# untitled.net
KiCad netlist of a schematic drawn in EAGLE
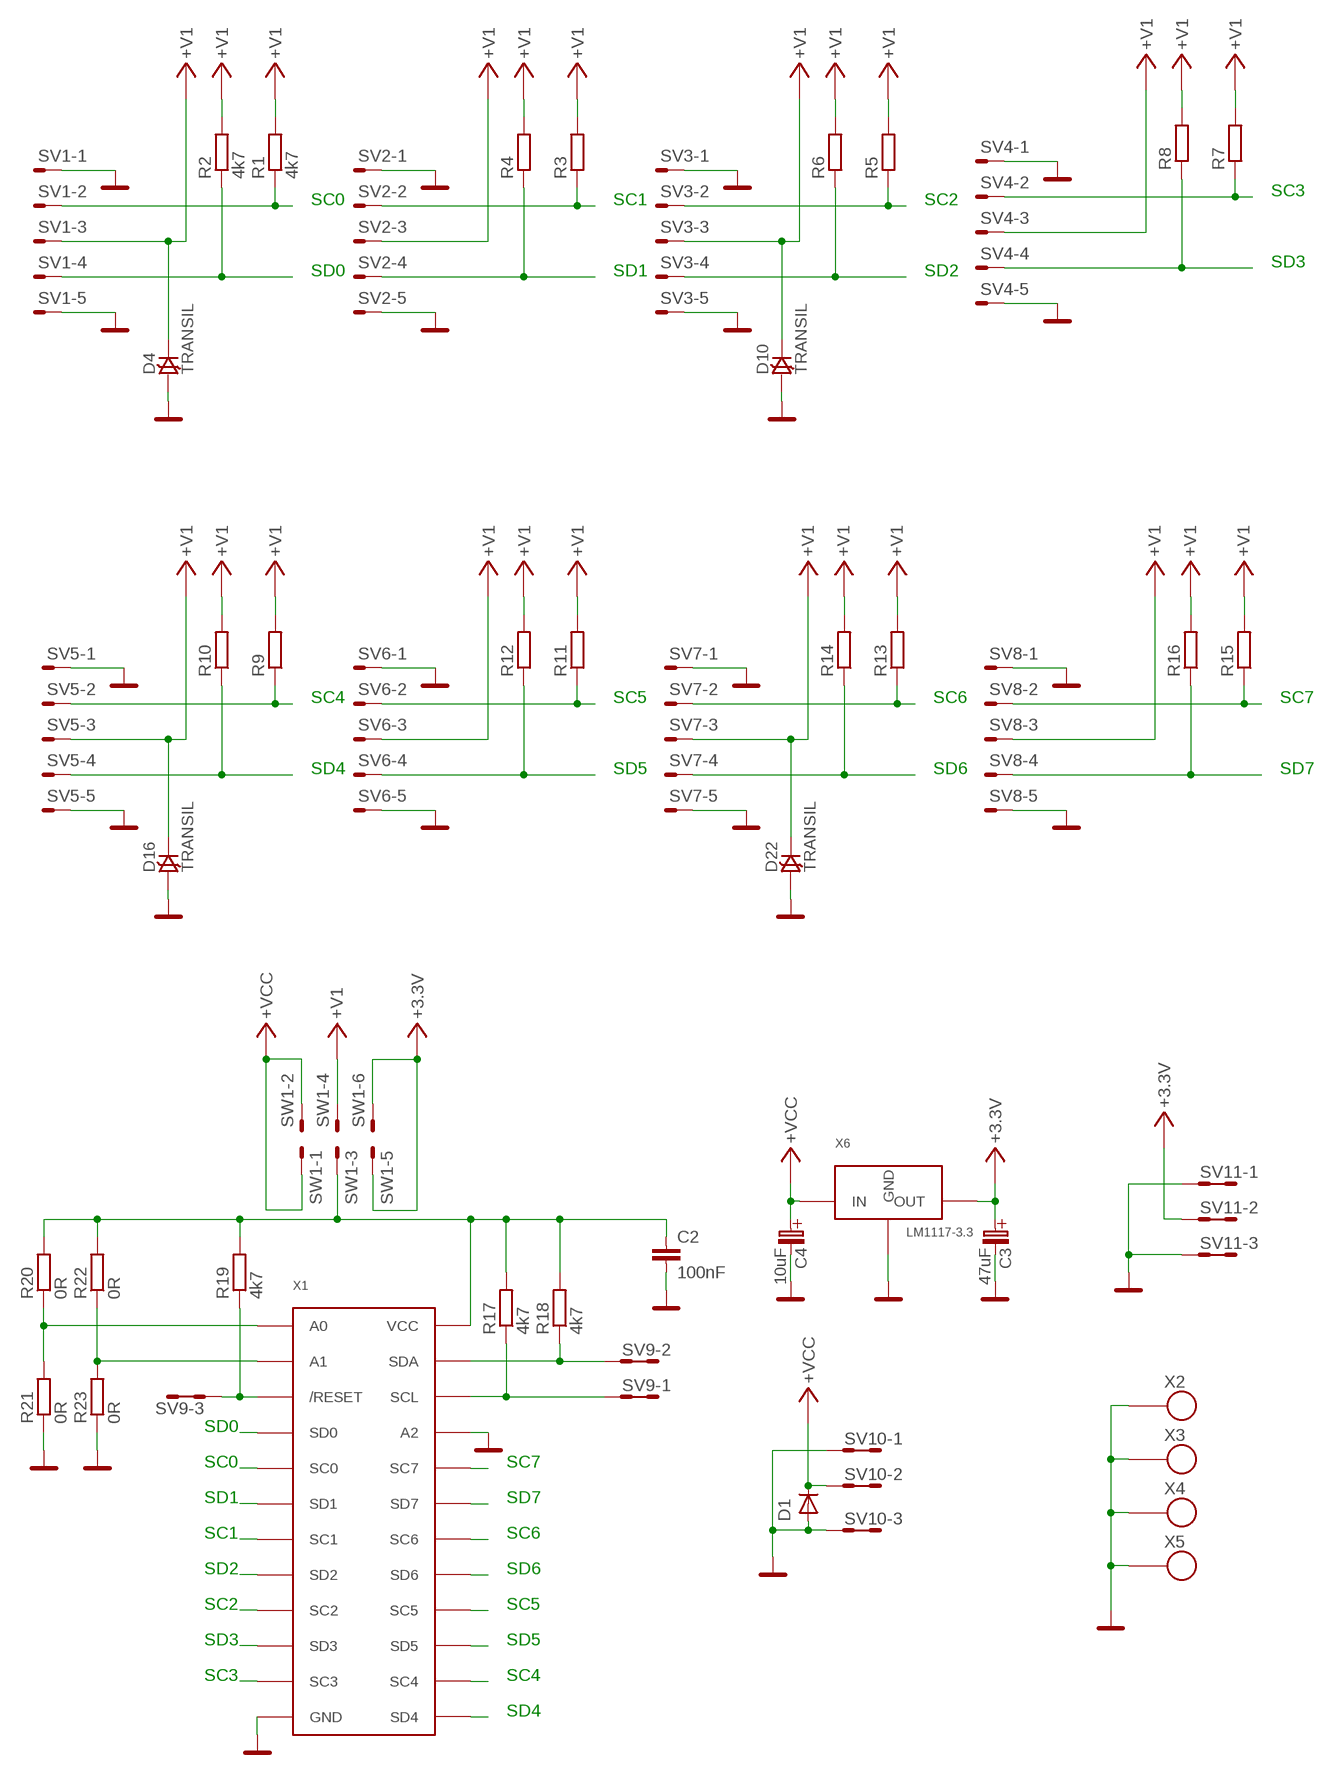
[diagram p0: schematic, sheet 1]

(export (version "E")
  (design (tool "Eeschema 10.0.6"))
  (components
    (comp (ref "C2")
      (value "100nF")
      (footprint "eagle-import:C0805")
      (libsource (lib "eagle-import") (part "C0805"))
    )
    (comp (ref "C3") (value "47uF") (footprint "eagle-import:C") (libsource (lib "eagle-import") (part "C")))
    (comp (ref "C4") (value "10uF") (footprint "eagle-import:B") (libsource (lib "eagle-import") (part "B")))
    (comp (ref "D1")
      (value "D-OB.SMA")
      (footprint "eagle-import:SMA")
      (libsource (lib "eagle-import") (part "D-OB.SMA"))
    )
    (comp (ref "D4")
      (value "TRANSIL")
      (footprint "eagle-import:SMA")
      (libsource (lib "eagle-import") (part "D-TRANSIL-SMA"))
    )
    (comp (ref "D10")
      (value "TRANSIL")
      (footprint "eagle-import:SMA")
      (libsource (lib "eagle-import") (part "D-TRANSIL-SMA"))
    )
    (comp (ref "D16")
      (value "TRANSIL")
      (footprint "eagle-import:SMA")
      (libsource (lib "eagle-import") (part "D-TRANSIL-SMA"))
    )
    (comp (ref "D22")
      (value "TRANSIL")
      (footprint "eagle-import:SMA")
      (libsource (lib "eagle-import") (part "D-TRANSIL-SMA"))
    )
    (comp (ref "R1")
      (value "4k7")
      (footprint "eagle-import:0805")
      (libsource (lib "eagle-import") (part "R0805"))
    )
    (comp (ref "R2")
      (value "4k7")
      (footprint "eagle-import:0805")
      (libsource (lib "eagle-import") (part "R0805"))
    )
    (comp (ref "R3")
      (value "R0805")
      (footprint "eagle-import:0805")
      (libsource (lib "eagle-import") (part "R0805"))
    )
    (comp (ref "R4")
      (value "R0805")
      (footprint "eagle-import:0805")
      (libsource (lib "eagle-import") (part "R0805"))
    )
    (comp (ref "R5")
      (value "R0805")
      (footprint "eagle-import:0805")
      (libsource (lib "eagle-import") (part "R0805"))
    )
    (comp (ref "R6")
      (value "R0805")
      (footprint "eagle-import:0805")
      (libsource (lib "eagle-import") (part "R0805"))
    )
    (comp (ref "R7")
      (value "R0805")
      (footprint "eagle-import:0805")
      (libsource (lib "eagle-import") (part "R0805"))
    )
    (comp (ref "R8")
      (value "R0805")
      (footprint "eagle-import:0805")
      (libsource (lib "eagle-import") (part "R0805"))
    )
    (comp (ref "R9")
      (value "R0805")
      (footprint "eagle-import:0805")
      (libsource (lib "eagle-import") (part "R0805"))
    )
    (comp (ref "R10")
      (value "R0805")
      (footprint "eagle-import:0805")
      (libsource (lib "eagle-import") (part "R0805"))
    )
    (comp (ref "R11")
      (value "R0805")
      (footprint "eagle-import:0805")
      (libsource (lib "eagle-import") (part "R0805"))
    )
    (comp (ref "R12")
      (value "R0805")
      (footprint "eagle-import:0805")
      (libsource (lib "eagle-import") (part "R0805"))
    )
    (comp (ref "R13")
      (value "R0805")
      (footprint "eagle-import:0805")
      (libsource (lib "eagle-import") (part "R0805"))
    )
    (comp (ref "R14")
      (value "R0805")
      (footprint "eagle-import:0805")
      (libsource (lib "eagle-import") (part "R0805"))
    )
    (comp (ref "R15")
      (value "R0805")
      (footprint "eagle-import:0805")
      (libsource (lib "eagle-import") (part "R0805"))
    )
    (comp (ref "R16")
      (value "R0805")
      (footprint "eagle-import:0805")
      (libsource (lib "eagle-import") (part "R0805"))
    )
    (comp (ref "R17")
      (value "4k7")
      (footprint "eagle-import:0805")
      (libsource (lib "eagle-import") (part "R0805"))
    )
    (comp (ref "R18")
      (value "4k7")
      (footprint "eagle-import:0805")
      (libsource (lib "eagle-import") (part "R0805"))
    )
    (comp (ref "R19")
      (value "4k7")
      (footprint "eagle-import:0805")
      (libsource (lib "eagle-import") (part "R0805"))
    )
    (comp (ref "R20")
      (value "0R")
      (footprint "eagle-import:0805")
      (libsource (lib "eagle-import") (part "R0805"))
    )
    (comp (ref "R21")
      (value "0R")
      (footprint "eagle-import:0805")
      (libsource (lib "eagle-import") (part "R0805"))
    )
    (comp (ref "R22")
      (value "0R")
      (footprint "eagle-import:0805")
      (libsource (lib "eagle-import") (part "R0805"))
    )
    (comp (ref "R23")
      (value "0R")
      (footprint "eagle-import:0805")
      (libsource (lib "eagle-import") (part "R0805"))
    )
    (comp (ref "SV1")
      (value "MA05-1")
      (footprint "eagle-import:MA05-1")
      (libsource (lib "eagle-import") (part "MA05-1"))
    )
    (comp (ref "SV2")
      (value "MA05-1")
      (footprint "eagle-import:MA05-1")
      (libsource (lib "eagle-import") (part "MA05-1"))
    )
    (comp (ref "SV3")
      (value "MA05-1")
      (footprint "eagle-import:MA05-1")
      (libsource (lib "eagle-import") (part "MA05-1"))
    )
    (comp (ref "SV4")
      (value "MA05-1")
      (footprint "eagle-import:MA05-1")
      (libsource (lib "eagle-import") (part "MA05-1"))
    )
    (comp (ref "SV5")
      (value "MA05-1")
      (footprint "eagle-import:MA05-1")
      (libsource (lib "eagle-import") (part "MA05-1"))
    )
    (comp (ref "SV6")
      (value "MA05-1")
      (footprint "eagle-import:MA05-1")
      (libsource (lib "eagle-import") (part "MA05-1"))
    )
    (comp (ref "SV7")
      (value "MA05-1")
      (footprint "eagle-import:MA05-1")
      (libsource (lib "eagle-import") (part "MA05-1"))
    )
    (comp (ref "SV8")
      (value "MA05-1")
      (footprint "eagle-import:MA05-1")
      (libsource (lib "eagle-import") (part "MA05-1"))
    )
    (comp (ref "SV9")
      (value "MA03-2")
      (footprint "eagle-import:MA03-2")
      (libsource (lib "eagle-import") (part "MA03-2"))
    )
    (comp (ref "SV10")
      (value "MA03-2")
      (footprint "eagle-import:MA03-2")
      (libsource (lib "eagle-import") (part "MA03-2"))
    )
    (comp (ref "SV11")
      (value "MA03-2")
      (footprint "eagle-import:MA03-2")
      (libsource (lib "eagle-import") (part "MA03-2"))
    )
    (comp (ref "SW1")
      (value "MA03-3")
      (footprint "eagle-import:MA03-2")
      (libsource (lib "eagle-import") (part "MA03-3"))
    )
    (comp (ref "X1")
      (value "TCA9548A")
      (footprint "eagle-import:TSS0P24")
      (libsource (lib "eagle-import") (part "TCA9548A"))
    )
    (comp (ref "X2")
      (value "SROUB3M")
      (footprint "eagle-import:SROUB3M")
      (libsource (lib "eagle-import") (part "SROUB3M"))
    )
    (comp (ref "X3")
      (value "SROUB3M")
      (footprint "eagle-import:SROUB3M")
      (libsource (lib "eagle-import") (part "SROUB3M"))
    )
    (comp (ref "X4")
      (value "SROUB3M")
      (footprint "eagle-import:SROUB3M")
      (libsource (lib "eagle-import") (part "SROUB3M"))
    )
    (comp (ref "X5")
      (value "SROUB3M")
      (footprint "eagle-import:SROUB3M")
      (libsource (lib "eagle-import") (part "SROUB3M"))
    )
    (comp (ref "X6")
      (value "LM1117-3.3")
      (footprint "eagle-import:SOT223")
      (libsource (lib "eagle-import") (part "LM1117"))
    )
  )
  (nets
    (net (code "1") (name "+3.3V") (class "Default")
      (node (ref "C3") (pin "+") (pinfunction "C_EL+_+") (pintype "passive"))
      (node (ref "SV11") (pin "3") (pinfunction "K_3") (pintype "passive"))
      (node (ref "SV11") (pin "4") (pinfunction "K_4") (pintype "passive"))
      (node (ref "SW1") (pin "5") (pinfunction "P$1_5") (pintype "passive"))
      (node (ref "SW1") (pin "6") (pinfunction "P$1_6") (pintype "passive"))
      (node (ref "X6") (pin "2") (pinfunction "OUT_2") (pintype "bidirectional"))
      (node (ref "X6") (pin "4") (pinfunction "OUT_4") (pintype "bidirectional"))
    )
    (net (code "2") (name "+V1") (class "Default")
      (node (ref "D10") (pin "K") (pinfunction "K_K") (pintype "passive"))
      (node (ref "D16") (pin "K") (pinfunction "K_K") (pintype "passive"))
      (node (ref "D22") (pin "K") (pinfunction "K_K") (pintype "passive"))
      (node (ref "D4") (pin "K") (pinfunction "K_K") (pintype "passive"))
      (node (ref "R1") (pin "2") (pinfunction "2_2") (pintype "passive"))
      (node (ref "R10") (pin "2") (pinfunction "2_2") (pintype "passive"))
      (node (ref "R11") (pin "2") (pinfunction "2_2") (pintype "passive"))
      (node (ref "R12") (pin "2") (pinfunction "2_2") (pintype "passive"))
      (node (ref "R13") (pin "2") (pinfunction "2_2") (pintype "passive"))
      (node (ref "R14") (pin "2") (pinfunction "2_2") (pintype "passive"))
      (node (ref "R15") (pin "2") (pinfunction "2_2") (pintype "passive"))
      (node (ref "R16") (pin "2") (pinfunction "2_2") (pintype "passive"))
      (node (ref "R2") (pin "2") (pinfunction "2_2") (pintype "passive"))
      (node (ref "R3") (pin "2") (pinfunction "2_2") (pintype "passive"))
      (node (ref "R4") (pin "2") (pinfunction "2_2") (pintype "passive"))
      (node (ref "R5") (pin "2") (pinfunction "2_2") (pintype "passive"))
      (node (ref "R6") (pin "2") (pinfunction "2_2") (pintype "passive"))
      (node (ref "R7") (pin "2") (pinfunction "2_2") (pintype "passive"))
      (node (ref "R8") (pin "2") (pinfunction "2_2") (pintype "passive"))
      (node (ref "R9") (pin "2") (pinfunction "2_2") (pintype "passive"))
      (node (ref "SV1") (pin "3") (pinfunction "P$1_3") (pintype "passive"))
      (node (ref "SV2") (pin "3") (pinfunction "P$1_3") (pintype "passive"))
      (node (ref "SV3") (pin "3") (pinfunction "P$1_3") (pintype "passive"))
      (node (ref "SV4") (pin "3") (pinfunction "P$1_3") (pintype "passive"))
      (node (ref "SV5") (pin "3") (pinfunction "P$1_3") (pintype "passive"))
      (node (ref "SV6") (pin "3") (pinfunction "P$1_3") (pintype "passive"))
      (node (ref "SV7") (pin "3") (pinfunction "P$1_3") (pintype "passive"))
      (node (ref "SV8") (pin "3") (pinfunction "P$1_3") (pintype "passive"))
      (node (ref "SW1") (pin "4") (pinfunction "P$1_4") (pintype "passive"))
    )
    (net (code "3") (name "+VCC") (class "Default")
      (node (ref "C4") (pin "+") (pinfunction "C_EL+_+") (pintype "passive"))
      (node (ref "D1") (pin "K") (pinfunction "C_K") (pintype "passive"))
      (node (ref "SV10") (pin "3") (pinfunction "K_3") (pintype "passive"))
      (node (ref "SV10") (pin "4") (pinfunction "K_4") (pintype "passive"))
      (node (ref "SW1") (pin "1") (pinfunction "P$1_1") (pintype "passive"))
      (node (ref "SW1") (pin "2") (pinfunction "P$1_2") (pintype "passive"))
      (node (ref "X6") (pin "3") (pinfunction "IN_3") (pintype "bidirectional"))
    )
    (net (code "4") (name "/SC0") (class "Default")
      (node (ref "R1") (pin "1") (pinfunction "1_1") (pintype "passive"))
      (node (ref "SV1") (pin "2") (pinfunction "P$1_2") (pintype "passive"))
      (node (ref "X1") (pin "5") (pinfunction "SC0_5") (pintype "bidirectional"))
    )
    (net (code "5") (name "/SC1") (class "Default")
      (node (ref "R3") (pin "1") (pinfunction "1_1") (pintype "passive"))
      (node (ref "SV2") (pin "2") (pinfunction "P$1_2") (pintype "passive"))
      (node (ref "X1") (pin "7") (pinfunction "SC1_7") (pintype "bidirectional"))
    )
    (net (code "6") (name "/SC2") (class "Default")
      (node (ref "R5") (pin "1") (pinfunction "1_1") (pintype "passive"))
      (node (ref "SV3") (pin "2") (pinfunction "P$1_2") (pintype "passive"))
      (node (ref "X1") (pin "9") (pinfunction "SC2_9") (pintype "bidirectional"))
    )
    (net (code "7") (name "/SC3") (class "Default")
      (node (ref "R7") (pin "1") (pinfunction "1_1") (pintype "passive"))
      (node (ref "SV4") (pin "2") (pinfunction "P$1_2") (pintype "passive"))
      (node (ref "X1") (pin "11") (pinfunction "SC3_11") (pintype "bidirectional"))
    )
    (net (code "8") (name "/SC4") (class "Default")
      (node (ref "R9") (pin "1") (pinfunction "1_1") (pintype "passive"))
      (node (ref "SV5") (pin "2") (pinfunction "P$1_2") (pintype "passive"))
      (node (ref "X1") (pin "14") (pinfunction "SC4_14") (pintype "bidirectional"))
    )
    (net (code "9") (name "/SC5") (class "Default")
      (node (ref "R11") (pin "1") (pinfunction "1_1") (pintype "passive"))
      (node (ref "SV6") (pin "2") (pinfunction "P$1_2") (pintype "passive"))
      (node (ref "X1") (pin "16") (pinfunction "SC5_16") (pintype "bidirectional"))
    )
    (net (code "10") (name "/SC6") (class "Default")
      (node (ref "R13") (pin "1") (pinfunction "1_1") (pintype "passive"))
      (node (ref "SV7") (pin "2") (pinfunction "P$1_2") (pintype "passive"))
      (node (ref "X1") (pin "18") (pinfunction "SC6_18") (pintype "bidirectional"))
    )
    (net (code "11") (name "/SC7") (class "Default")
      (node (ref "R15") (pin "1") (pinfunction "1_1") (pintype "passive"))
      (node (ref "SV8") (pin "2") (pinfunction "P$1_2") (pintype "passive"))
      (node (ref "X1") (pin "20") (pinfunction "SC7_20") (pintype "bidirectional"))
    )
    (net (code "12") (name "/SD0") (class "Default")
      (node (ref "R2") (pin "1") (pinfunction "1_1") (pintype "passive"))
      (node (ref "SV1") (pin "4") (pinfunction "P$1_4") (pintype "passive"))
      (node (ref "X1") (pin "4") (pinfunction "SD0_4") (pintype "bidirectional"))
    )
    (net (code "13") (name "/SD1") (class "Default")
      (node (ref "R4") (pin "1") (pinfunction "1_1") (pintype "passive"))
      (node (ref "SV2") (pin "4") (pinfunction "P$1_4") (pintype "passive"))
      (node (ref "X1") (pin "6") (pinfunction "SD1_6") (pintype "bidirectional"))
    )
    (net (code "14") (name "/SD2") (class "Default")
      (node (ref "R6") (pin "1") (pinfunction "1_1") (pintype "passive"))
      (node (ref "SV3") (pin "4") (pinfunction "P$1_4") (pintype "passive"))
      (node (ref "X1") (pin "8") (pinfunction "SD2_8") (pintype "bidirectional"))
    )
    (net (code "15") (name "/SD3") (class "Default")
      (node (ref "R8") (pin "1") (pinfunction "1_1") (pintype "passive"))
      (node (ref "SV4") (pin "4") (pinfunction "P$1_4") (pintype "passive"))
      (node (ref "X1") (pin "10") (pinfunction "SD3_10") (pintype "bidirectional"))
    )
    (net (code "16") (name "/SD4") (class "Default")
      (node (ref "R10") (pin "1") (pinfunction "1_1") (pintype "passive"))
      (node (ref "SV5") (pin "4") (pinfunction "P$1_4") (pintype "passive"))
      (node (ref "X1") (pin "13") (pinfunction "SD4_13") (pintype "bidirectional"))
    )
    (net (code "17") (name "/SD5") (class "Default")
      (node (ref "R12") (pin "1") (pinfunction "1_1") (pintype "passive"))
      (node (ref "SV6") (pin "4") (pinfunction "P$1_4") (pintype "passive"))
      (node (ref "X1") (pin "15") (pinfunction "SD5_15") (pintype "bidirectional"))
    )
    (net (code "18") (name "/SD6") (class "Default")
      (node (ref "R14") (pin "1") (pinfunction "1_1") (pintype "passive"))
      (node (ref "SV7") (pin "4") (pinfunction "P$1_4") (pintype "passive"))
      (node (ref "X1") (pin "17") (pinfunction "SD6_17") (pintype "bidirectional"))
    )
    (net (code "19") (name "/SD7") (class "Default")
      (node (ref "R16") (pin "1") (pinfunction "1_1") (pintype "passive"))
      (node (ref "SV8") (pin "4") (pinfunction "P$1_4") (pintype "passive"))
      (node (ref "X1") (pin "19") (pinfunction "SD7_19") (pintype "bidirectional"))
    )
    (net (code "20") (name "GND") (class "Default")
      (node (ref "C2") (pin "2") (pinfunction "2_2") (pintype "passive"))
      (node (ref "C3") (pin "-") (pinfunction "C_EL-_-") (pintype "passive"))
      (node (ref "C4") (pin "-") (pinfunction "C_EL-_-") (pintype "passive"))
      (node (ref "D1") (pin "A") (pinfunction "A_A") (pintype "passive"))
      (node (ref "D10") (pin "A") (pinfunction "A_A") (pintype "passive"))
      (node (ref "D16") (pin "A") (pinfunction "A_A") (pintype "passive"))
      (node (ref "D22") (pin "A") (pinfunction "A_A") (pintype "passive"))
      (node (ref "D4") (pin "A") (pinfunction "A_A") (pintype "passive"))
      (node (ref "R21") (pin "1") (pinfunction "1_1") (pintype "passive"))
      (node (ref "R23") (pin "1") (pinfunction "1_1") (pintype "passive"))
      (node (ref "SV1") (pin "1") (pinfunction "P$1_1") (pintype "passive"))
      (node (ref "SV1") (pin "5") (pinfunction "P$1_5") (pintype "passive"))
      (node (ref "SV10") (pin "1") (pinfunction "K_1") (pintype "passive"))
      (node (ref "SV10") (pin "2") (pinfunction "K_2") (pintype "passive"))
      (node (ref "SV10") (pin "5") (pinfunction "K_5") (pintype "passive"))
      (node (ref "SV10") (pin "6") (pinfunction "K_6") (pintype "passive"))
      (node (ref "SV11") (pin "1") (pinfunction "K_1") (pintype "passive"))
      (node (ref "SV11") (pin "2") (pinfunction "K_2") (pintype "passive"))
      (node (ref "SV11") (pin "5") (pinfunction "K_5") (pintype "passive"))
      (node (ref "SV11") (pin "6") (pinfunction "K_6") (pintype "passive"))
      (node (ref "SV2") (pin "1") (pinfunction "P$1_1") (pintype "passive"))
      (node (ref "SV2") (pin "5") (pinfunction "P$1_5") (pintype "passive"))
      (node (ref "SV3") (pin "1") (pinfunction "P$1_1") (pintype "passive"))
      (node (ref "SV3") (pin "5") (pinfunction "P$1_5") (pintype "passive"))
      (node (ref "SV4") (pin "1") (pinfunction "P$1_1") (pintype "passive"))
      (node (ref "SV4") (pin "5") (pinfunction "P$1_5") (pintype "passive"))
      (node (ref "SV5") (pin "1") (pinfunction "P$1_1") (pintype "passive"))
      (node (ref "SV5") (pin "5") (pinfunction "P$1_5") (pintype "passive"))
      (node (ref "SV6") (pin "1") (pinfunction "P$1_1") (pintype "passive"))
      (node (ref "SV6") (pin "5") (pinfunction "P$1_5") (pintype "passive"))
      (node (ref "SV7") (pin "1") (pinfunction "P$1_1") (pintype "passive"))
      (node (ref "SV7") (pin "5") (pinfunction "P$1_5") (pintype "passive"))
      (node (ref "SV8") (pin "1") (pinfunction "P$1_1") (pintype "passive"))
      (node (ref "SV8") (pin "5") (pinfunction "P$1_5") (pintype "passive"))
      (node (ref "X1") (pin "12") (pinfunction "GND_12") (pintype "bidirectional"))
      (node (ref "X1") (pin "21") (pinfunction "A2_21") (pintype "bidirectional"))
      (node (ref "X2") (pin "P$1") (pinfunction "P$1_P$1") (pintype "bidirectional"))
      (node (ref "X3") (pin "P$1") (pinfunction "P$1_P$1") (pintype "bidirectional"))
      (node (ref "X4") (pin "P$1") (pinfunction "P$1_P$1") (pintype "bidirectional"))
      (node (ref "X5") (pin "P$1") (pinfunction "P$1_P$1") (pintype "bidirectional"))
      (node (ref "X6") (pin "1") (pinfunction "GND_1") (pintype "bidirectional"))
    )
    (net (code "21") (name "Net-(SW1C-P$1)") (class "Default")
      (node (ref "C2") (pin "1") (pinfunction "1_1") (pintype "passive"))
      (node (ref "R17") (pin "2") (pinfunction "2_2") (pintype "passive"))
      (node (ref "R18") (pin "2") (pinfunction "2_2") (pintype "passive"))
      (node (ref "R19") (pin "2") (pinfunction "2_2") (pintype "passive"))
      (node (ref "R20") (pin "2") (pinfunction "2_2") (pintype "passive"))
      (node (ref "R22") (pin "2") (pinfunction "2_2") (pintype "passive"))
      (node (ref "SW1") (pin "3") (pinfunction "P$1_3") (pintype "passive"))
      (node (ref "X1") (pin "24") (pinfunction "VCC_24") (pintype "bidirectional"))
    )
    (net (code "22") (name "Net-(X1-A0)") (class "Default")
      (node (ref "R20") (pin "1") (pinfunction "1_1") (pintype "passive"))
      (node (ref "R21") (pin "2") (pinfunction "2_2") (pintype "passive"))
      (node (ref "X1") (pin "1") (pinfunction "A0_1") (pintype "bidirectional"))
    )
    (net (code "23") (name "Net-(X1-A1)") (class "Default")
      (node (ref "R22") (pin "1") (pinfunction "1_1") (pintype "passive"))
      (node (ref "R23") (pin "2") (pinfunction "2_2") (pintype "passive"))
      (node (ref "X1") (pin "2") (pinfunction "A1_2") (pintype "bidirectional"))
    )
    (net (code "24") (name "Net-(X1-SCL)") (class "Default")
      (node (ref "R17") (pin "1") (pinfunction "1_1") (pintype "passive"))
      (node (ref "SV9") (pin "1") (pinfunction "K_1") (pintype "passive"))
      (node (ref "SV9") (pin "2") (pinfunction "K_2") (pintype "passive"))
      (node (ref "X1") (pin "22") (pinfunction "SCL_22") (pintype "bidirectional"))
    )
    (net (code "25") (name "Net-(X1-SDA)") (class "Default")
      (node (ref "R18") (pin "1") (pinfunction "1_1") (pintype "passive"))
      (node (ref "SV9") (pin "3") (pinfunction "K_3") (pintype "passive"))
      (node (ref "SV9") (pin "4") (pinfunction "K_4") (pintype "passive"))
      (node (ref "X1") (pin "23") (pinfunction "SDA_23") (pintype "bidirectional"))
    )
    (net (code "26") (name "Net-(X1-{slash}RESET)") (class "Default")
      (node (ref "R19") (pin "1") (pinfunction "1_1") (pintype "passive"))
      (node (ref "SV9") (pin "5") (pinfunction "K_5") (pintype "passive"))
      (node (ref "SV9") (pin "6") (pinfunction "K_6") (pintype "passive"))
      (node (ref "X1") (pin "3") (pinfunction "/RESET_3") (pintype "bidirectional"))
    )
  )
)
